# untitled.net
KiCad netlist of a schematic drawn in EAGLE
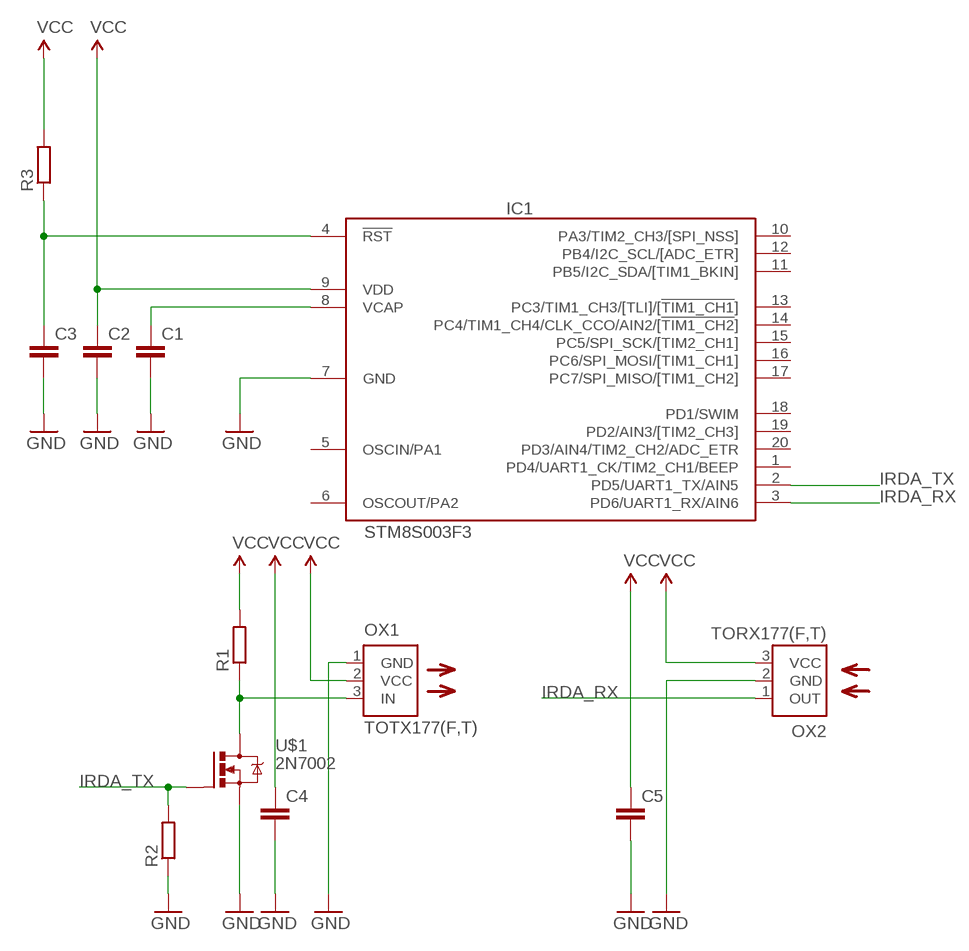
[diagram p0: schematic, sheet 1]

(export (version "E")
  (design (tool "Eeschema 10.0.6"))
  (components
    (comp (ref "C1")
      (value "CC0805")
      (footprint "eagle-import:C0805")
      (libsource (lib "eagle-import") (part "CC0805"))
    )
    (comp (ref "C2")
      (value "CC0805")
      (footprint "eagle-import:C0805")
      (libsource (lib "eagle-import") (part "CC0805"))
    )
    (comp (ref "C3")
      (value "CC0603")
      (footprint "eagle-import:C0603")
      (libsource (lib "eagle-import") (part "CC0603"))
    )
    (comp (ref "C4")
      (value "CC0805")
      (footprint "eagle-import:C0805")
      (libsource (lib "eagle-import") (part "CC0805"))
    )
    (comp (ref "C5")
      (value "CC0805")
      (footprint "eagle-import:C0805")
      (libsource (lib "eagle-import") (part "CC0805"))
    )
    (comp (ref "IC1")
      (value "STM8S003F3")
      (footprint "eagle-import:TSSOP20")
      (libsource (lib "eagle-import") (part "STM8S003F3"))
    )
    (comp (ref "OX1")
      (value "TOTX177(F,T)")
      (footprint "eagle-import:TOTX")
      (libsource (lib "eagle-import") (part "TOTX177(F,T)"))
    )
    (comp (ref "OX2")
      (value "TORX177(F,T)")
      (footprint "eagle-import:TORX")
      (libsource (lib "eagle-import") (part "TORX177(F,T)"))
    )
    (comp (ref "R1")
      (value "R0603")
      (footprint "eagle-import:0603")
      (libsource (lib "eagle-import") (part "R0603"))
    )
    (comp (ref "R2")
      (value "R0603")
      (footprint "eagle-import:0603")
      (libsource (lib "eagle-import") (part "R0603"))
    )
    (comp (ref "R3")
      (value "R0603")
      (footprint "eagle-import:0603")
      (libsource (lib "eagle-import") (part "R0603"))
    )
    (comp (ref "U$1")
      (value "2N7002")
      (footprint "eagle-import:SOT23")
      (libsource (lib "eagle-import") (part "2N7002"))
    )
  )
  (nets
    (net (code "1") (name "/IRDA_RX") (class "Default")
      (node (ref "IC1") (pin "3") (pinfunction "PD6/UART1_RX/AIN6_3") (pintype "bidirectional"))
      (node (ref "OX2") (pin "1") (pinfunction "OUT_1") (pintype "output"))
    )
    (net (code "2") (name "/IRDA_TX") (class "Default")
      (node (ref "IC1") (pin "2") (pinfunction "PD5/UART1_TX/AIN5_2") (pintype "bidirectional"))
      (node (ref "R2") (pin "2") (pinfunction "2_2") (pintype "passive"))
      (node (ref "U$1") (pin "1") (pinfunction "G_1") (pintype "passive"))
    )
    (net (code "3") (name "GND") (class "Default")
      (node (ref "C1") (pin "2") (pinfunction "2_2") (pintype "passive"))
      (node (ref "C2") (pin "2") (pinfunction "2_2") (pintype "passive"))
      (node (ref "C3") (pin "2") (pinfunction "2_2") (pintype "passive"))
      (node (ref "C4") (pin "2") (pinfunction "2_2") (pintype "passive"))
      (node (ref "C5") (pin "2") (pinfunction "2_2") (pintype "passive"))
      (node (ref "IC1") (pin "7") (pinfunction "GND_7") (pintype "power_in"))
      (node (ref "OX1") (pin "1") (pinfunction "GND_1") (pintype "power_in"))
      (node (ref "OX2") (pin "2") (pinfunction "GND_2") (pintype "power_in"))
      (node (ref "R2") (pin "1") (pinfunction "1_1") (pintype "passive"))
      (node (ref "U$1") (pin "2") (pinfunction "S_2") (pintype "passive"))
    )
    (net (code "4") (name "Net-(IC1-VCAP)") (class "Default")
      (node (ref "C1") (pin "1") (pinfunction "1_1") (pintype "passive"))
      (node (ref "IC1") (pin "8") (pinfunction "VCAP_8") (pintype "power_in"))
    )
    (net (code "5") (name "Net-(IC1-~{RST})") (class "Default")
      (node (ref "C3") (pin "1") (pinfunction "1_1") (pintype "passive"))
      (node (ref "IC1") (pin "4") (pinfunction "~{RST}_4") (pintype "input"))
      (node (ref "R3") (pin "1") (pinfunction "1_1") (pintype "passive"))
    )
    (net (code "6") (name "Net-(OX1-IN)") (class "Default")
      (node (ref "OX1") (pin "3") (pinfunction "IN_3") (pintype "input"))
      (node (ref "R1") (pin "1") (pinfunction "1_1") (pintype "passive"))
      (node (ref "U$1") (pin "3") (pinfunction "D_3") (pintype "passive"))
    )
    (net (code "7") (name "VCC") (class "Default")
      (node (ref "C2") (pin "1") (pinfunction "1_1") (pintype "passive"))
      (node (ref "C4") (pin "1") (pinfunction "1_1") (pintype "passive"))
      (node (ref "C5") (pin "1") (pinfunction "1_1") (pintype "passive"))
      (node (ref "IC1") (pin "9") (pinfunction "VDD_9") (pintype "power_in"))
      (node (ref "OX1") (pin "2") (pinfunction "VCC_2") (pintype "power_in"))
      (node (ref "OX2") (pin "3") (pinfunction "VCC_3") (pintype "power_in"))
      (node (ref "R1") (pin "2") (pinfunction "2_2") (pintype "passive"))
      (node (ref "R3") (pin "2") (pinfunction "2_2") (pintype "passive"))
    )
    (net (code "8") (name "unconnected-(IC1-OSCIN{slash}PA1-Pad5)") (class "Default")
      (node (ref "IC1") (pin "5") (pinfunction "OSCIN/PA1_5") (pintype "bidirectional"))
    )
    (net (code "9") (name "unconnected-(IC1-OSCOUT{slash}PA2-Pad6)") (class "Default")
      (node (ref "IC1") (pin "6") (pinfunction "OSCOUT/PA2_6") (pintype "bidirectional"))
    )
    (net (code "10") (name "unconnected-(IC1-PA3{slash}TIM2_CH3{slash}[SPI_NSS]-Pad10)") (class "Default")
      (node (ref "IC1") (pin "10") (pinfunction "PA3/TIM2_CH3/[SPI_NSS]_10") (pintype "bidirectional"))
    )
    (net (code "11") (name "unconnected-(IC1-PB4{slash}I2C_SCL{slash}[ADC_ETR]-Pad12)") (class "Default")
      (node (ref "IC1") (pin "12") (pinfunction "PB4/I2C_SCL/[ADC_ETR]_12") (pintype "bidirectional"))
    )
    (net (code "12") (name "unconnected-(IC1-PB5{slash}I2C_SDA{slash}[TIM1_BKIN]-Pad11)") (class "Default")
      (node (ref "IC1") (pin "11") (pinfunction "PB5/I2C_SDA/[TIM1_BKIN]_11") (pintype "bidirectional"))
    )
    (net (code "13") (name "unconnected-(IC1-PC3{slash}TIM1_CH3{slash}[TLI]{slash}[~{TIM1_CH1}]-Pad13)") (class "Default")
      (node (ref "IC1") (pin "13") (pinfunction "PC3/TIM1_CH3/[TLI]/[~{TIM1_CH1}]_13") (pintype "bidirectional"))
    )
    (net (code "14") (name "unconnected-(IC1-PC4{slash}TIM1_CH4{slash}CLK_CCO{slash}AIN2{slash}[~{TIM1_CH2}]-Pad14)") (class "Default")
      (node (ref "IC1") (pin "14") (pinfunction "PC4/TIM1_CH4/CLK_CCO/AIN2/[~{TIM1_CH2}]_14") (pintype "bidirectional"))
    )
    (net (code "15") (name "unconnected-(IC1-PC5{slash}SPI_SCK{slash}[TIM2_CH1]-Pad15)") (class "Default")
      (node (ref "IC1") (pin "15") (pinfunction "PC5/SPI_SCK/[TIM2_CH1]_15") (pintype "bidirectional"))
    )
    (net (code "16") (name "unconnected-(IC1-PC6{slash}SPI_MOSI{slash}[TIM1_CH1]-Pad16)") (class "Default")
      (node (ref "IC1") (pin "16") (pinfunction "PC6/SPI_MOSI/[TIM1_CH1]_16") (pintype "bidirectional"))
    )
    (net (code "17") (name "unconnected-(IC1-PC7{slash}SPI_MISO{slash}[TIM1_CH2]-Pad17)") (class "Default")
      (node (ref "IC1") (pin "17") (pinfunction "PC7/SPI_MISO/[TIM1_CH2]_17") (pintype "bidirectional"))
    )
    (net (code "18") (name "unconnected-(IC1-PD1{slash}SWIM-Pad18)") (class "Default")
      (node (ref "IC1") (pin "18") (pinfunction "PD1/SWIM_18") (pintype "bidirectional"))
    )
    (net (code "19") (name "unconnected-(IC1-PD2{slash}AIN3{slash}[TIM2_CH3]-Pad19)") (class "Default")
      (node (ref "IC1") (pin "19") (pinfunction "PD2/AIN3/[TIM2_CH3]_19") (pintype "bidirectional"))
    )
    (net (code "20") (name "unconnected-(IC1-PD3{slash}AIN4{slash}TIM2_CH2{slash}ADC_ETR-Pad20)") (class "Default")
      (node (ref "IC1") (pin "20") (pinfunction "PD3/AIN4/TIM2_CH2/ADC_ETR_20") (pintype "bidirectional"))
    )
    (net (code "21") (name "unconnected-(IC1-PD4{slash}UART1_CK{slash}TIM2_CH1{slash}BEEP-Pad1)") (class "Default")
      (node (ref "IC1") (pin "1") (pinfunction "PD4/UART1_CK/TIM2_CH1/BEEP_1") (pintype "bidirectional"))
    )
  )
)
